# pressure-sensor.net
KiCad netlist of a schematic drawn in Altium Designer
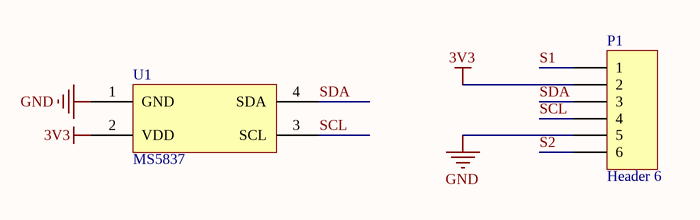
[diagram p0: pressure-sensor.SchDoc]

(export (version "E")
  (design (tool "Eeschema 10.0.6"))
  (components
    (comp (ref "P1")
      (value "Header 6")
      (footprint "HDR1X6")
      (description "Header, 6-Pin")
      (fields (field (name "PUBLISHER") "Altium Limited"))
      (libsource (lib "Miscellaneous Connectors") (part "Header 6"))
    )
    (comp (ref "U1")
      (value "MS5837")
      (footprint "MS5837")
      (fields
        (field (name "MANUFACTURER") "TE Connectivity")
        (field (name "MANUFACTURER PART NUMBER") "MS583730BA01-50")
      )
      (libsource (lib "pressure-sensor") (part "MS583730BA01-50"))
    )
  )
  (nets
    (net (code "1") (name "/S1") (class "Default")
      (node (ref "P1") (pin "1") (pinfunction "1_1") (pintype "passive"))
    )
    (net (code "2") (name "/S2") (class "Default")
      (node (ref "P1") (pin "6") (pinfunction "6_6") (pintype "passive"))
    )
    (net (code "3") (name "/SCL") (class "Default")
      (node (ref "P1") (pin "4") (pinfunction "4_4") (pintype "passive"))
      (node (ref "U1") (pin "3") (pinfunction "SCL_3") (pintype "open_collector"))
    )
    (net (code "4") (name "/SDA") (class "Default")
      (node (ref "P1") (pin "3") (pinfunction "3_3") (pintype "passive"))
      (node (ref "U1") (pin "4") (pinfunction "SDA_4") (pintype "open_collector"))
    )
    (net (code "5") (name "3V3") (class "Default")
      (node (ref "P1") (pin "2") (pinfunction "2_2") (pintype "passive"))
      (node (ref "U1") (pin "2") (pinfunction "VDD_2") (pintype "open_collector"))
    )
    (net (code "6") (name "GND") (class "Default")
      (node (ref "P1") (pin "5") (pinfunction "5_5") (pintype "passive"))
      (node (ref "U1") (pin "1") (pinfunction "GND_1") (pintype "open_collector"))
    )
  )
)
